# Motor_Driver.net
KiCad netlist of a schematic drawn in Altium Designer
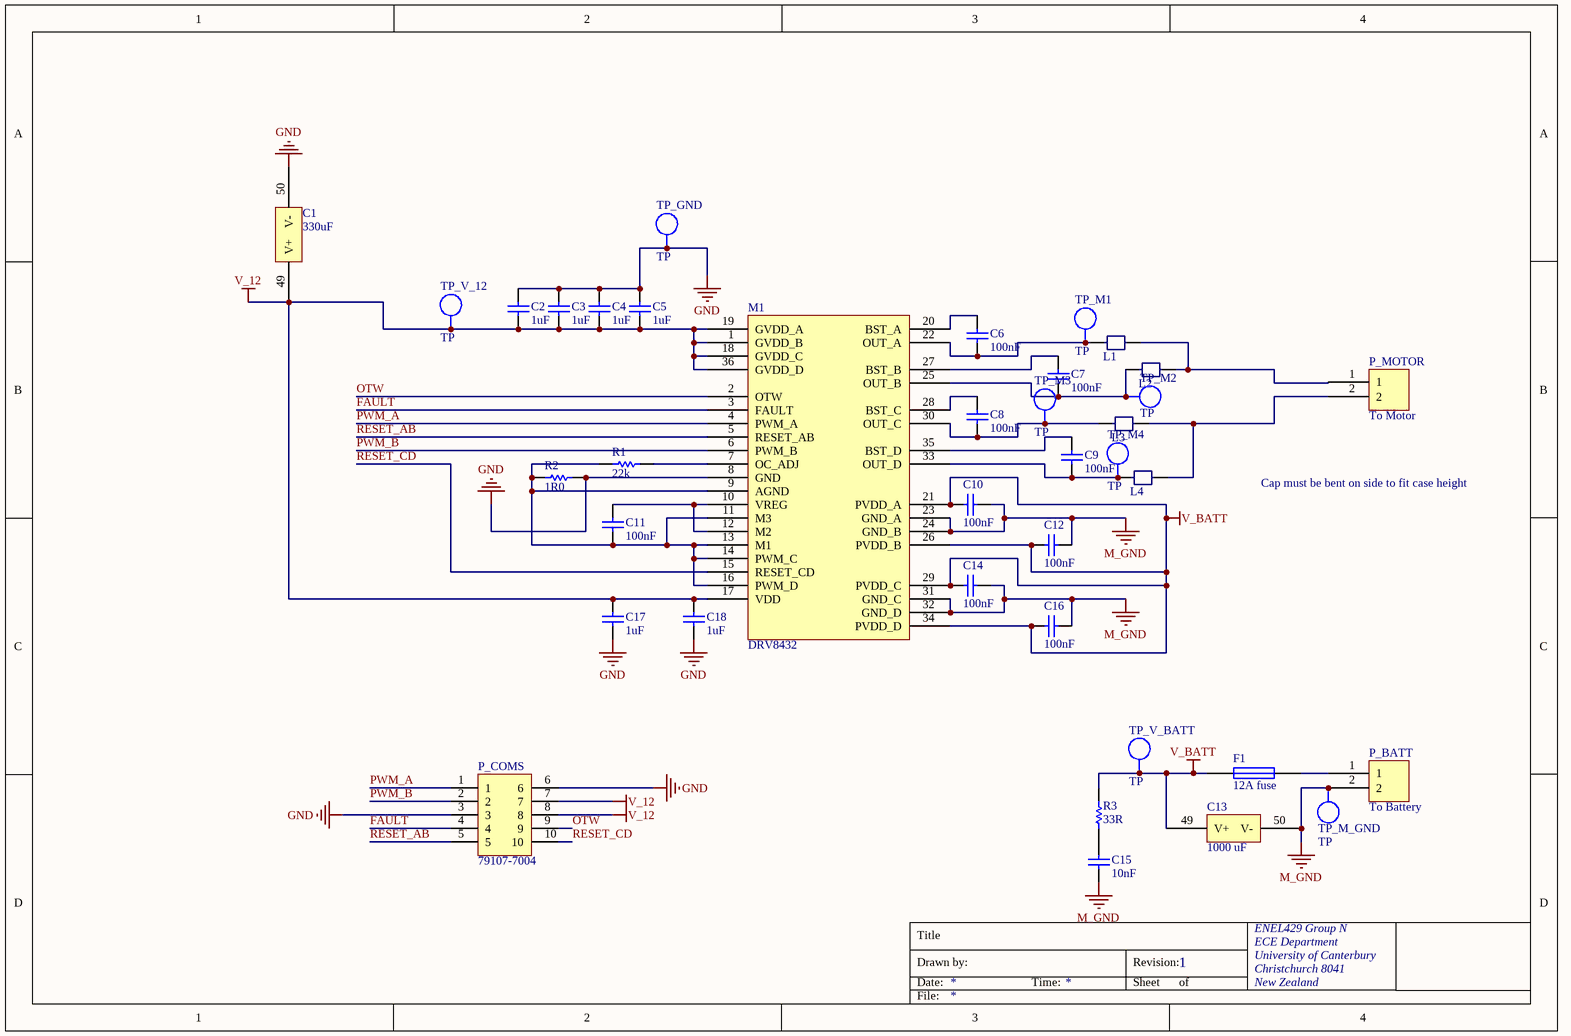
[diagram p0: Motor Driver.SchDoc]

(export (version "E")
  (design (tool "Eeschema 10.0.6"))
  (components
    (comp (ref "C1")
      (value "330uF")
      (footprint "330uF Capacitor")
      (fields
        (field (name "MANUFACTURER") "CORNELL DUBILIER")
        (field (name "MANUFACTURER PART NUMBER") "AVE337M16F24T-F")
      )
      (libsource (lib "MarioLib") (part "AVE337M16F24T-F"))
    )
    (comp (ref "C2")
      (value "1uF")
      (footprint "0603")
      (description "CAP CER 1.0UF 50V X7R 0603")
      (fields (field (name "MANUFACTURER") "Taiyo Yuden") (field (name "PART NUMBER") "CP_1uF_50V_0603"))
      (libsource (lib "ENEL429_4") (part "CP_1uF_50V_0603"))
    )
    (comp (ref "C3")
      (value "1uF")
      (footprint "0603")
      (description "CAP CER 1.0UF 50V X7R 0603")
      (fields (field (name "MANUFACTURER") "Taiyo Yuden") (field (name "PART NUMBER") "CP_1uF_50V_0603"))
      (libsource (lib "ENEL429_4") (part "CP_1uF_50V_0603"))
    )
    (comp (ref "C4")
      (value "1uF")
      (footprint "0603")
      (description "CAP CER 1.0UF 50V X7R 0603")
      (fields (field (name "MANUFACTURER") "Taiyo Yuden") (field (name "PART NUMBER") "CP_1uF_50V_0603"))
      (libsource (lib "ENEL429_4") (part "CP_1uF_50V_0603"))
    )
    (comp (ref "C5")
      (value "1uF")
      (footprint "0603")
      (description "CAP CER 1.0UF 50V X7R 0603")
      (fields (field (name "MANUFACTURER") "Taiyo Yuden") (field (name "PART NUMBER") "CP_1uF_50V_0603"))
      (libsource (lib "ENEL429_4") (part "CP_1uF_50V_0603"))
    )
    (comp (ref "C6")
      (value "100nF")
      (footprint "0603")
      (description "CAP CER .10UF 50V X5R 0603")
      (fields (field (name "MANUFACTURER") "Taiyo Yuden") (field (name "PART NUMBER") "CP_100nF 0603"))
      (libsource (lib "ENEL429_4") (part "CP_100nF 0603"))
    )
    (comp (ref "C7")
      (value "100nF")
      (footprint "0603")
      (description "CAP CER .10UF 50V X5R 0603")
      (fields (field (name "MANUFACTURER") "Taiyo Yuden") (field (name "PART NUMBER") "CP_100nF 0603"))
      (libsource (lib "ENEL429_4") (part "CP_100nF 0603"))
    )
    (comp (ref "C8")
      (value "100nF")
      (footprint "0603")
      (description "CAP CER .10UF 50V X5R 0603")
      (fields (field (name "MANUFACTURER") "Taiyo Yuden") (field (name "PART NUMBER") "CP_100nF 0603"))
      (libsource (lib "ENEL429_4") (part "CP_100nF 0603"))
    )
    (comp (ref "C9")
      (value "100nF")
      (footprint "0603")
      (description "CAP CER .10UF 50V X5R 0603")
      (fields (field (name "MANUFACTURER") "Taiyo Yuden") (field (name "PART NUMBER") "CP_100nF 0603"))
      (libsource (lib "ENEL429_4") (part "CP_100nF 0603"))
    )
    (comp (ref "C10")
      (value "100nF")
      (footprint "0603")
      (description "CAP CER .10UF 50V X5R 0603")
      (fields (field (name "MANUFACTURER") "Taiyo Yuden") (field (name "PART NUMBER") "CP_100nF 0603"))
      (libsource (lib "ENEL429_4") (part "CP_100nF 0603"))
    )
    (comp (ref "C11")
      (value "100nF")
      (footprint "0603")
      (description "CAP CER .10UF 50V X5R 0603")
      (fields (field (name "MANUFACTURER") "Taiyo Yuden") (field (name "PART NUMBER") "CP_100nF 0603"))
      (libsource (lib "ENEL429_4") (part "CP_100nF 0603"))
    )
    (comp (ref "C12")
      (value "100nF")
      (footprint "0603")
      (description "CAP CER .10UF 50V X5R 0603")
      (fields (field (name "MANUFACTURER") "Taiyo Yuden") (field (name "PART NUMBER") "CP_100nF 0603"))
      (libsource (lib "ENEL429_4") (part "CP_100nF 0603"))
    )
    (comp (ref "C13")
      (value "1000 uF")
      (footprint "Capacitor 1000uF")
      (libsource (lib "MarioLib") (part "EEUFK1V102L"))
    )
    (comp (ref "C14")
      (value "100nF")
      (footprint "0603")
      (description "CAP CER .10UF 50V X5R 0603")
      (fields (field (name "MANUFACTURER") "Taiyo Yuden") (field (name "PART NUMBER") "CP_100nF 0603"))
      (libsource (lib "ENEL429_4") (part "CP_100nF 0603"))
    )
    (comp (ref "C15")
      (value "10nF")
      (footprint "0603")
      (description "CAP CER 10000PF 100V X7R 0603")
      (fields (field (name "MANUFACTURER") "Taiyo Yuden") (field (name "PART NUMBER") "CP_10nF 0603"))
      (libsource (lib "ENEL429_4") (part "CP_10nF 0603"))
    )
    (comp (ref "C16")
      (value "100nF")
      (footprint "0603")
      (description "CAP CER .10UF 50V X5R 0603")
      (fields (field (name "MANUFACTURER") "Taiyo Yuden") (field (name "PART NUMBER") "CP_100nF 0603"))
      (libsource (lib "ENEL429_4") (part "CP_100nF 0603"))
    )
    (comp (ref "C17")
      (value "1uF")
      (footprint "0603")
      (description "CAP CER 1.0UF 50V X7R 0603")
      (fields (field (name "MANUFACTURER") "Taiyo Yuden") (field (name "PART NUMBER") "CP_1uF_50V_0603"))
      (libsource (lib "ENEL429_4") (part "CP_1uF_50V_0603"))
    )
    (comp (ref "C18")
      (value "1uF")
      (footprint "0603")
      (description "CAP CER 1.0UF 50V X7R 0603")
      (fields (field (name "MANUFACTURER") "Taiyo Yuden") (field (name "PART NUMBER") "CP_1uF_50V_0603"))
      (libsource (lib "ENEL429_4") (part "CP_1uF_50V_0603"))
    )
    (comp (ref "F1")
      (value "12A fuse")
      (footprint "RESC3216L")
      (description "Fuse")
      (fields (field (name "PUBLISHER") "Altium Limited"))
      (libsource (lib "Miscellaneous Devices") (part "Fuse 1"))
    )
    (comp (ref "L1")
      (value "FERRITE BEAD 10A")
      (description "FERRITE 10A 56 OHM 1612 SMD")
      (libsource (lib "MarioLib") (part "10A Ferrite bead"))
    )
    (comp (ref "L2")
      (value "FERRITE BEAD 10A")
      (description "FERRITE 10A 56 OHM 1612 SMD")
      (libsource (lib "MarioLib") (part "10A Ferrite bead"))
    )
    (comp (ref "L3")
      (value "FERRITE BEAD 10A")
      (description "FERRITE 10A 56 OHM 1612 SMD")
      (libsource (lib "MarioLib") (part "10A Ferrite bead"))
    )
    (comp (ref "L4")
      (value "FERRITE BEAD 10A")
      (description "FERRITE 10A 56 OHM 1612 SMD")
      (libsource (lib "MarioLib") (part "10A Ferrite bead"))
    )
    (comp (ref "M1")
      (value "DRV8432")
      (footprint "DRV8432")
      (description "Motor Driver")
      (libsource (lib "MarioLib") (part "DRV8432"))
    )
    (comp (ref "P_BATT")
      (value "To Battery")
      (footprint "0010844020")
      (libsource (lib "MarioLib") (part "Power Header"))
    )
    (comp (ref "P_COMS")
      (value "79107-7004")
      (footprint "79107-7004")
      (description "CONN RECEPT 2MM 10POS VERT")
      (fields (field (name "MANUFACTURER") "Molex"))
      (libsource (lib "MarioLib") (part "79107-7004"))
    )
    (comp (ref "P_MOTOR")
      (value "To Motor")
      (footprint "0010844020")
      (libsource (lib "MarioLib") (part "Power Header"))
    )
    (comp (ref "R1")
      (value "22k")
      (footprint "0603")
      (description "RES 22.0K OHM 1/10W 1% 0603 SMD")
      (fields (field (name "MANUFACTURER") "Yageo") (field (name "PART NUMBER") "RS_22k 0603"))
      (libsource (lib "ENEL429_4") (part "RS_22k 0603"))
    )
    (comp (ref "R2")
      (value "1R0")
      (footprint "0603")
      (description "RES 1R0 OHM 1/10W 1% 0603 SMD")
      (fields (field (name "MANUFACTURER") "Yageo") (field (name "PART NUMBER") "RS_1R0 0603"))
      (libsource (lib "ENEL429_4") (part "RS_1R0 0603"))
    )
    (comp (ref "R3")
      (value "33R")
      (footprint "0603")
      (description "RES 33 OHM 1/10W 1% 0603 SMD")
      (fields (field (name "MANUFACTURER") "Yageo") (field (name "PART NUMBER") "RS_33R 0603"))
      (libsource (lib "ENEL429_4") (part "RS_33R 0603"))
    )
    (comp (ref "TP_GND")
      (value "TP")
      (footprint "TEST_POINT_4X2MM")
      (description "Test-Point")
      (fields (field (name "PART NUMBER") "TP_TESTPOINT"))
      (libsource (lib "ENEL429_4") (part "TP_TESTPOINT"))
    )
    (comp (ref "TP_M1")
      (value "TP")
      (footprint "TEST_POINT_4X2MM")
      (description "Test-Point")
      (fields (field (name "PART NUMBER") "TP_TESTPOINT"))
      (libsource (lib "ENEL429_4") (part "TP_TESTPOINT"))
    )
    (comp (ref "TP_M2")
      (value "TP")
      (footprint "TEST_POINT_4X2MM")
      (description "Test-Point")
      (fields (field (name "PART NUMBER") "TP_TESTPOINT"))
      (libsource (lib "ENEL429_4") (part "TP_TESTPOINT"))
    )
    (comp (ref "TP_M3")
      (value "TP")
      (footprint "TEST_POINT_4X2MM")
      (description "Test-Point")
      (fields (field (name "PART NUMBER") "TP_TESTPOINT"))
      (libsource (lib "ENEL429_4") (part "TP_TESTPOINT"))
    )
    (comp (ref "TP_M4")
      (value "TP")
      (footprint "TEST_POINT_4X2MM")
      (description "Test-Point")
      (fields (field (name "PART NUMBER") "TP_TESTPOINT"))
      (libsource (lib "ENEL429_4") (part "TP_TESTPOINT"))
    )
    (comp (ref "TP_M_GND")
      (value "TP")
      (footprint "TEST_POINT_4X2MM")
      (description "Test-Point")
      (fields (field (name "PART NUMBER") "TP_TESTPOINT"))
      (libsource (lib "ENEL429_4") (part "TP_TESTPOINT"))
    )
    (comp (ref "TP_V_12")
      (value "TP")
      (footprint "TEST_POINT_4X2MM")
      (description "Test-Point")
      (fields (field (name "PART NUMBER") "TP_TESTPOINT"))
      (libsource (lib "ENEL429_4") (part "TP_TESTPOINT"))
    )
    (comp (ref "TP_V_BATT")
      (value "TP")
      (footprint "TEST_POINT_4X2MM")
      (description "Test-Point")
      (fields (field (name "PART NUMBER") "TP_TESTPOINT"))
      (libsource (lib "ENEL429_4") (part "TP_TESTPOINT"))
    )
  )
  (nets
    (net (code "1") (name "/FAULT") (class "Default")
      (node (ref "M1") (pin "3") (pinfunction "FAULT_3") (pintype "passive"))
      (node (ref "P_COMS") (pin "4") (pinfunction "4_4") (pintype "passive"))
    )
    (net (code "2") (name "/OTW") (class "Default")
      (node (ref "M1") (pin "2") (pinfunction "OTW_2") (pintype "passive"))
      (node (ref "P_COMS") (pin "9") (pinfunction "9_9") (pintype "passive"))
    )
    (net (code "3") (name "/PWM_A") (class "Default")
      (node (ref "M1") (pin "4") (pinfunction "PWM_A_4") (pintype "passive"))
      (node (ref "P_COMS") (pin "1") (pinfunction "1_1") (pintype "passive"))
    )
    (net (code "4") (name "/PWM_B") (class "Default")
      (node (ref "M1") (pin "6") (pinfunction "PWM_B_6") (pintype "passive"))
      (node (ref "P_COMS") (pin "2") (pinfunction "2_2") (pintype "passive"))
    )
    (net (code "5") (name "/RESET_AB") (class "Default")
      (node (ref "M1") (pin "5") (pinfunction "RESET_AB_5") (pintype "passive"))
      (node (ref "P_COMS") (pin "5") (pinfunction "5_5") (pintype "passive"))
    )
    (net (code "6") (name "/RESET_CD") (class "Default")
      (node (ref "M1") (pin "15") (pinfunction "RESET_CD_15") (pintype "passive"))
      (node (ref "P_COMS") (pin "10") (pinfunction "10_10") (pintype "passive"))
    )
    (net (code "7") (name "GND") (class "Default")
      (node (ref "C1") (pin "50") (pinfunction "V-_50") (pintype "passive"))
      (node (ref "C17") (pin "2") (pinfunction "2_2") (pintype "passive"))
      (node (ref "C18") (pin "2") (pinfunction "2_2") (pintype "passive"))
      (node (ref "C2") (pin "1") (pinfunction "1_1") (pintype "passive"))
      (node (ref "C3") (pin "1") (pinfunction "1_1") (pintype "passive"))
      (node (ref "C4") (pin "1") (pinfunction "1_1") (pintype "passive"))
      (node (ref "C5") (pin "1") (pinfunction "1_1") (pintype "passive"))
      (node (ref "M1") (pin "8") (pinfunction "GND_8") (pintype "passive"))
      (node (ref "P_COMS") (pin "3") (pinfunction "3_3") (pintype "passive"))
      (node (ref "P_COMS") (pin "6") (pinfunction "6_6") (pintype "passive"))
      (node (ref "R2") (pin "2") (pinfunction "2_2") (pintype "passive"))
      (node (ref "TP_GND") (pin "1") (pinfunction "1_1") (pintype "passive"))
    )
    (net (code "8") (name "M_GND") (class "Default")
      (node (ref "C10") (pin "1") (pinfunction "1_1") (pintype "passive"))
      (node (ref "C12") (pin "1") (pinfunction "1_1") (pintype "passive"))
      (node (ref "C13") (pin "50") (pinfunction "V-_50") (pintype "passive"))
      (node (ref "C14") (pin "1") (pinfunction "1_1") (pintype "passive"))
      (node (ref "C15") (pin "1") (pinfunction "1_1") (pintype "passive"))
      (node (ref "C16") (pin "1") (pinfunction "1_1") (pintype "passive"))
      (node (ref "M1") (pin "23") (pinfunction "GND_A_23") (pintype "passive"))
      (node (ref "M1") (pin "24") (pinfunction "GND_B_24") (pintype "passive"))
      (node (ref "M1") (pin "31") (pinfunction "GND_C_31") (pintype "passive"))
      (node (ref "M1") (pin "32") (pinfunction "GND_D_32") (pintype "passive"))
      (node (ref "P_BATT") (pin "2") (pinfunction "2_2") (pintype "passive"))
      (node (ref "TP_M_GND") (pin "1") (pinfunction "1_1") (pintype "passive"))
    )
    (net (code "9") (name "Net-(C15-Pad2)") (class "Default")
      (node (ref "C15") (pin "2") (pinfunction "2_2") (pintype "passive"))
      (node (ref "R3") (pin "1") (pinfunction "1_1") (pintype "passive"))
    )
    (net (code "10") (name "Net-(F1-Pad2)") (class "Default")
      (node (ref "F1") (pin "2") (pinfunction "2_2") (pintype "passive"))
      (node (ref "P_BATT") (pin "1") (pinfunction "1_1") (pintype "passive"))
    )
    (net (code "11") (name "Net-(L1-Pad2)") (class "Default")
      (node (ref "L1") (pin "2") (pinfunction "2_2") (pintype "passive"))
      (node (ref "L2") (pin "2") (pinfunction "2_2") (pintype "passive"))
      (node (ref "P_MOTOR") (pin "1") (pinfunction "1_1") (pintype "passive"))
    )
    (net (code "12") (name "Net-(L3-Pad2)") (class "Default")
      (node (ref "L3") (pin "2") (pinfunction "2_2") (pintype "passive"))
      (node (ref "L4") (pin "2") (pinfunction "2_2") (pintype "passive"))
      (node (ref "P_MOTOR") (pin "2") (pinfunction "2_2") (pintype "passive"))
    )
    (net (code "13") (name "Net-(M1-AGND)") (class "Default")
      (node (ref "C11") (pin "1") (pinfunction "1_1") (pintype "passive"))
      (node (ref "M1") (pin "11") (pinfunction "M3_11") (pintype "passive"))
      (node (ref "M1") (pin "13") (pinfunction "M1_13") (pintype "passive"))
      (node (ref "M1") (pin "14") (pinfunction "PWM_C_14") (pintype "passive"))
      (node (ref "M1") (pin "16") (pinfunction "PWM_D_16") (pintype "passive"))
      (node (ref "M1") (pin "9") (pinfunction "AGND_9") (pintype "passive"))
      (node (ref "R1") (pin "1") (pinfunction "1_1") (pintype "passive"))
      (node (ref "R2") (pin "1") (pinfunction "1_1") (pintype "passive"))
    )
    (net (code "14") (name "Net-(M1-BST_A)") (class "Default")
      (node (ref "C6") (pin "2") (pinfunction "2_2") (pintype "passive"))
      (node (ref "M1") (pin "20") (pinfunction "BST_A_20") (pintype "passive"))
    )
    (net (code "15") (name "Net-(M1-BST_B)") (class "Default")
      (node (ref "C7") (pin "2") (pinfunction "2_2") (pintype "passive"))
      (node (ref "M1") (pin "27") (pinfunction "BST_B_27") (pintype "passive"))
    )
    (net (code "16") (name "Net-(M1-BST_C)") (class "Default")
      (node (ref "C8") (pin "2") (pinfunction "2_2") (pintype "passive"))
      (node (ref "M1") (pin "28") (pinfunction "BST_C_28") (pintype "passive"))
    )
    (net (code "17") (name "Net-(M1-BST_D)") (class "Default")
      (node (ref "C9") (pin "2") (pinfunction "2_2") (pintype "passive"))
      (node (ref "M1") (pin "35") (pinfunction "BST_D_35") (pintype "passive"))
    )
    (net (code "18") (name "Net-(M1-M2)") (class "Default")
      (node (ref "C11") (pin "2") (pinfunction "2_2") (pintype "passive"))
      (node (ref "M1") (pin "10") (pinfunction "VREG_10") (pintype "passive"))
      (node (ref "M1") (pin "12") (pinfunction "M2_12") (pintype "passive"))
    )
    (net (code "19") (name "Net-(M1-OC_ADJ)") (class "Default")
      (node (ref "M1") (pin "7") (pinfunction "OC_ADJ_7") (pintype "passive"))
      (node (ref "R1") (pin "2") (pinfunction "2_2") (pintype "passive"))
    )
    (net (code "20") (name "Net-(M1-OUT_A)") (class "Default")
      (node (ref "C6") (pin "1") (pinfunction "1_1") (pintype "passive"))
      (node (ref "L1") (pin "1") (pinfunction "1_1") (pintype "passive"))
      (node (ref "M1") (pin "22") (pinfunction "OUT_A_22") (pintype "passive"))
      (node (ref "TP_M1") (pin "1") (pinfunction "1_1") (pintype "passive"))
    )
    (net (code "21") (name "Net-(M1-OUT_B)") (class "Default")
      (node (ref "C7") (pin "1") (pinfunction "1_1") (pintype "passive"))
      (node (ref "L2") (pin "1") (pinfunction "1_1") (pintype "passive"))
      (node (ref "M1") (pin "25") (pinfunction "OUT_B_25") (pintype "passive"))
      (node (ref "TP_M2") (pin "1") (pinfunction "1_1") (pintype "passive"))
    )
    (net (code "22") (name "Net-(M1-OUT_C)") (class "Default")
      (node (ref "C8") (pin "1") (pinfunction "1_1") (pintype "passive"))
      (node (ref "L3") (pin "1") (pinfunction "1_1") (pintype "passive"))
      (node (ref "M1") (pin "30") (pinfunction "OUT_C_30") (pintype "passive"))
      (node (ref "TP_M3") (pin "1") (pinfunction "1_1") (pintype "passive"))
    )
    (net (code "23") (name "Net-(M1-OUT_D)") (class "Default")
      (node (ref "C9") (pin "1") (pinfunction "1_1") (pintype "passive"))
      (node (ref "L4") (pin "1") (pinfunction "1_1") (pintype "passive"))
      (node (ref "M1") (pin "33") (pinfunction "OUT_D_33") (pintype "passive"))
      (node (ref "TP_M4") (pin "1") (pinfunction "1_1") (pintype "passive"))
    )
    (net (code "24") (name "V_12") (class "Default")
      (node (ref "C1") (pin "49") (pinfunction "V+_49") (pintype "passive"))
      (node (ref "C17") (pin "1") (pinfunction "1_1") (pintype "passive"))
      (node (ref "C18") (pin "1") (pinfunction "1_1") (pintype "passive"))
      (node (ref "C2") (pin "2") (pinfunction "2_2") (pintype "passive"))
      (node (ref "C3") (pin "2") (pinfunction "2_2") (pintype "passive"))
      (node (ref "C4") (pin "2") (pinfunction "2_2") (pintype "passive"))
      (node (ref "C5") (pin "2") (pinfunction "2_2") (pintype "passive"))
      (node (ref "M1") (pin "1") (pinfunction "GVDD_B_1") (pintype "passive"))
      (node (ref "M1") (pin "17") (pinfunction "VDD_17") (pintype "passive"))
      (node (ref "M1") (pin "18") (pinfunction "GVDD_C_18") (pintype "passive"))
      (node (ref "M1") (pin "19") (pinfunction "GVDD_A_19") (pintype "passive"))
      (node (ref "M1") (pin "36") (pinfunction "GVDD_D_36") (pintype "passive"))
      (node (ref "P_COMS") (pin "7") (pinfunction "7_7") (pintype "passive"))
      (node (ref "P_COMS") (pin "8") (pinfunction "8_8") (pintype "passive"))
      (node (ref "TP_V_12") (pin "1") (pinfunction "1_1") (pintype "passive"))
    )
    (net (code "25") (name "V_BATT") (class "Default")
      (node (ref "C10") (pin "2") (pinfunction "2_2") (pintype "passive"))
      (node (ref "C12") (pin "2") (pinfunction "2_2") (pintype "passive"))
      (node (ref "C13") (pin "49") (pinfunction "V+_49") (pintype "passive"))
      (node (ref "C14") (pin "2") (pinfunction "2_2") (pintype "passive"))
      (node (ref "C16") (pin "2") (pinfunction "2_2") (pintype "passive"))
      (node (ref "F1") (pin "1") (pinfunction "1_1") (pintype "passive"))
      (node (ref "M1") (pin "21") (pinfunction "PVDD_A_21") (pintype "passive"))
      (node (ref "M1") (pin "26") (pinfunction "PVDD_B_26") (pintype "passive"))
      (node (ref "M1") (pin "29") (pinfunction "PVDD_C_29") (pintype "passive"))
      (node (ref "M1") (pin "34") (pinfunction "PVDD_D_34") (pintype "passive"))
      (node (ref "R3") (pin "2") (pinfunction "2_2") (pintype "passive"))
      (node (ref "TP_V_BATT") (pin "1") (pinfunction "1_1") (pintype "passive"))
    )
  )
)
